# ARA_Cartridge_V4.net
KiCad netlist of a schematic drawn in EAGLE
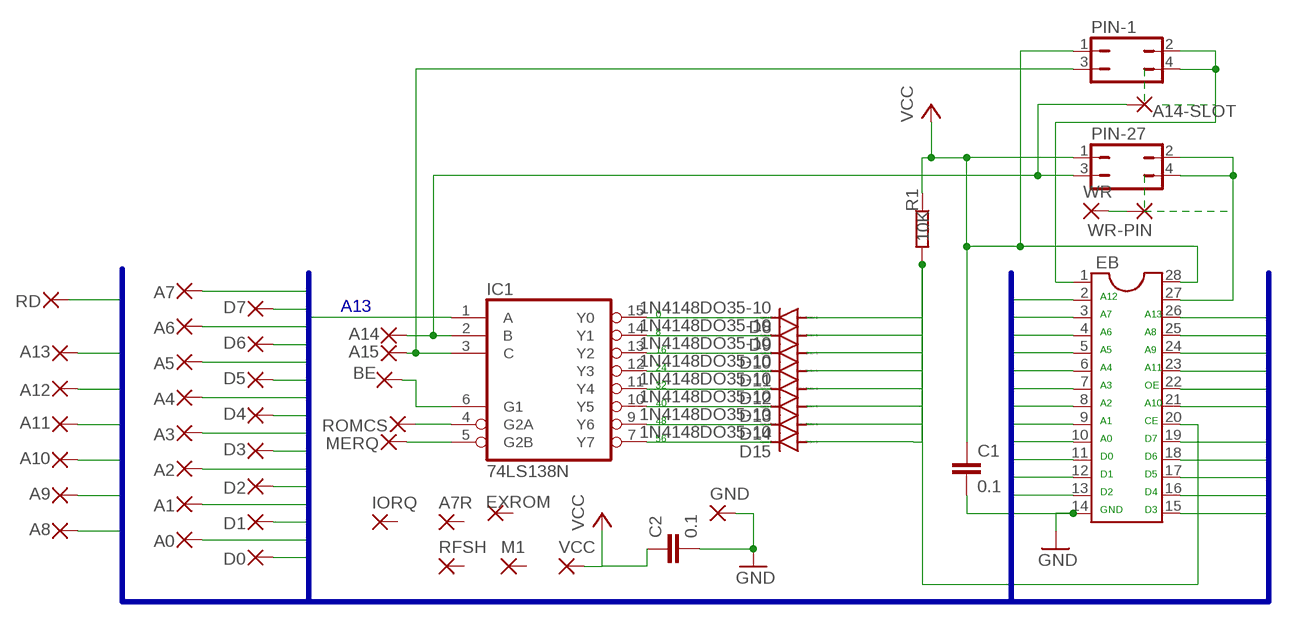
[diagram p0: schematic, sheet 1]

(export (version "E")
  (design (tool "Eeschema 10.0.6"))
  (components
    (comp (ref "A0")
      (value "SMD2")
      (footprint "eagle-import:SMD2")
      (libsource (lib "eagle-import") (part "SMD2"))
    )
    (comp (ref "A1")
      (value "SMD2")
      (footprint "eagle-import:SMD2")
      (libsource (lib "eagle-import") (part "SMD2"))
    )
    (comp (ref "A2")
      (value "SMD2")
      (footprint "eagle-import:SMD2")
      (libsource (lib "eagle-import") (part "SMD2"))
    )
    (comp (ref "A3")
      (value "SMD2")
      (footprint "eagle-import:SMD2")
      (libsource (lib "eagle-import") (part "SMD2"))
    )
    (comp (ref "A4")
      (value "SMD2")
      (footprint "eagle-import:SMD2")
      (libsource (lib "eagle-import") (part "SMD2"))
    )
    (comp (ref "A5")
      (value "SMD2")
      (footprint "eagle-import:SMD2")
      (libsource (lib "eagle-import") (part "SMD2"))
    )
    (comp (ref "A6")
      (value "SMD2")
      (footprint "eagle-import:SMD2")
      (libsource (lib "eagle-import") (part "SMD2"))
    )
    (comp (ref "A7")
      (value "SMD2")
      (footprint "eagle-import:SMD2")
      (libsource (lib "eagle-import") (part "SMD2"))
    )
    (comp (ref "A7R")
      (value "SMD2")
      (footprint "eagle-import:SMD2")
      (libsource (lib "eagle-import") (part "SMD2"))
    )
    (comp (ref "A8")
      (value "SMD2")
      (footprint "eagle-import:SMD2")
      (libsource (lib "eagle-import") (part "SMD2"))
    )
    (comp (ref "A9")
      (value "SMD2")
      (footprint "eagle-import:SMD2")
      (libsource (lib "eagle-import") (part "SMD2"))
    )
    (comp (ref "A10")
      (value "SMD2")
      (footprint "eagle-import:SMD2")
      (libsource (lib "eagle-import") (part "SMD2"))
    )
    (comp (ref "A11")
      (value "SMD2")
      (footprint "eagle-import:SMD2")
      (libsource (lib "eagle-import") (part "SMD2"))
    )
    (comp (ref "A12")
      (value "SMD2")
      (footprint "eagle-import:SMD2")
      (libsource (lib "eagle-import") (part "SMD2"))
    )
    (comp (ref "A13")
      (value "SMD2")
      (footprint "eagle-import:SMD2")
      (libsource (lib "eagle-import") (part "SMD2"))
    )
    (comp (ref "A14")
      (value "SMD2")
      (footprint "eagle-import:SMD2")
      (libsource (lib "eagle-import") (part "SMD2"))
    )
    (comp (ref "A14-SLOT")
      (value "1,6/0,8")
      (footprint "eagle-import:1,6_0,8")
      (libsource (lib "eagle-import") (part "1,6/0,8"))
    )
    (comp (ref "A15")
      (value "SMD2")
      (footprint "eagle-import:SMD2")
      (libsource (lib "eagle-import") (part "SMD2"))
    )
    (comp (ref "BE")
      (value "SMD2")
      (footprint "eagle-import:SMD2")
      (libsource (lib "eagle-import") (part "SMD2"))
    )
    (comp (ref "C1")
      (value "0.1")
      (footprint "eagle-import:C2.5-3")
      (libsource (lib "eagle-import") (part "C2,5-3"))
    )
    (comp (ref "C2")
      (value "0.1")
      (footprint "eagle-import:C2.5-3")
      (libsource (lib "eagle-import") (part "C2,5-3"))
    )
    (comp (ref "D0")
      (value "SMD2")
      (footprint "eagle-import:SMD2")
      (libsource (lib "eagle-import") (part "SMD2"))
    )
    (comp (ref "D1")
      (value "SMD2")
      (footprint "eagle-import:SMD2")
      (libsource (lib "eagle-import") (part "SMD2"))
    )
    (comp (ref "D2")
      (value "SMD2")
      (footprint "eagle-import:SMD2")
      (libsource (lib "eagle-import") (part "SMD2"))
    )
    (comp (ref "D3")
      (value "SMD2")
      (footprint "eagle-import:SMD2")
      (libsource (lib "eagle-import") (part "SMD2"))
    )
    (comp (ref "D4")
      (value "SMD2")
      (footprint "eagle-import:SMD2")
      (libsource (lib "eagle-import") (part "SMD2"))
    )
    (comp (ref "D5")
      (value "SMD2")
      (footprint "eagle-import:SMD2")
      (libsource (lib "eagle-import") (part "SMD2"))
    )
    (comp (ref "D6")
      (value "SMD2")
      (footprint "eagle-import:SMD2")
      (libsource (lib "eagle-import") (part "SMD2"))
    )
    (comp (ref "D7")
      (value "SMD2")
      (footprint "eagle-import:SMD2")
      (libsource (lib "eagle-import") (part "SMD2"))
    )
    (comp (ref "D8")
      (value "1N4148DO35-10")
      (footprint "eagle-import:DO35-10")
      (libsource (lib "eagle-import") (part "1N4148DO35-10"))
    )
    (comp (ref "D9")
      (value "1N4148DO35-10")
      (footprint "eagle-import:DO35-10")
      (libsource (lib "eagle-import") (part "1N4148DO35-10"))
    )
    (comp (ref "D10")
      (value "1N4148DO35-10")
      (footprint "eagle-import:DO35-10")
      (libsource (lib "eagle-import") (part "1N4148DO35-10"))
    )
    (comp (ref "D11")
      (value "1N4148DO35-10")
      (footprint "eagle-import:DO35-10")
      (libsource (lib "eagle-import") (part "1N4148DO35-10"))
    )
    (comp (ref "D12")
      (value "1N4148DO35-10")
      (footprint "eagle-import:DO35-10")
      (libsource (lib "eagle-import") (part "1N4148DO35-10"))
    )
    (comp (ref "D13")
      (value "1N4148DO35-10")
      (footprint "eagle-import:DO35-10")
      (libsource (lib "eagle-import") (part "1N4148DO35-10"))
    )
    (comp (ref "D14")
      (value "1N4148DO35-10")
      (footprint "eagle-import:DO35-10")
      (libsource (lib "eagle-import") (part "1N4148DO35-10"))
    )
    (comp (ref "D15")
      (value "1N4148DO35-10")
      (footprint "eagle-import:DO35-10")
      (libsource (lib "eagle-import") (part "1N4148DO35-10"))
    )
    (comp (ref "EB")
      (value "DIL28")
      (footprint "eagle-import:DIL28-6")
      (libsource (lib "eagle-import") (part "DIL28"))
    )
    (comp (ref "EXROM")
      (value "SMD2")
      (footprint "eagle-import:SMD2")
      (libsource (lib "eagle-import") (part "SMD2"))
    )
    (comp (ref "GND")
      (value "SMD2")
      (footprint "eagle-import:SMD2")
      (libsource (lib "eagle-import") (part "SMD2"))
    )
    (comp (ref "IC1")
      (value "74LS138N")
      (footprint "eagle-import:DIL16")
      (libsource (lib "eagle-import") (part "74138NLS"))
    )
    (comp (ref "IORQ")
      (value "SMD2")
      (footprint "eagle-import:SMD2")
      (libsource (lib "eagle-import") (part "SMD2"))
    )
    (comp (ref "M1")
      (value "SMD2")
      (footprint "eagle-import:SMD2")
      (libsource (lib "eagle-import") (part "SMD2"))
    )
    (comp (ref "MERQ")
      (value "SMD2")
      (footprint "eagle-import:SMD2")
      (libsource (lib "eagle-import") (part "SMD2"))
    )
    (comp (ref "PIN-1")
      (value "JP2Q")
      (footprint "eagle-import:JP2Q")
      (libsource (lib "eagle-import") (part "JP2Q"))
    )
    (comp (ref "PIN-27")
      (value "JP2Q")
      (footprint "eagle-import:JP2Q")
      (libsource (lib "eagle-import") (part "JP2Q"))
    )
    (comp (ref "R1")
      (value "10K")
      (footprint "eagle-import:0207_10")
      (libsource (lib "eagle-import") (part "R-EU_0207/10"))
    )
    (comp (ref "RD")
      (value "SMD2")
      (footprint "eagle-import:SMD2")
      (libsource (lib "eagle-import") (part "SMD2"))
    )
    (comp (ref "RFSH")
      (value "SMD2")
      (footprint "eagle-import:SMD2")
      (libsource (lib "eagle-import") (part "SMD2"))
    )
    (comp (ref "ROMCS")
      (value "SMD2")
      (footprint "eagle-import:SMD2")
      (libsource (lib "eagle-import") (part "SMD2"))
    )
    (comp (ref "VCC")
      (value "SMD2")
      (footprint "eagle-import:SMD2")
      (libsource (lib "eagle-import") (part "SMD2"))
    )
    (comp (ref "WR")
      (value "SMD2")
      (footprint "eagle-import:SMD2")
      (libsource (lib "eagle-import") (part "SMD2"))
    )
    (comp (ref "WR-PIN")
      (value "1,6/0,8")
      (footprint "eagle-import:1,6_0,8")
      (libsource (lib "eagle-import") (part "1,6/0,8"))
    )
  )
  (nets
    (net (code "1") (name "/A0") (class "Default")
      (node (ref "A0") (pin "1") (pinfunction "P_1") (pintype "passive"))
      (node (ref "EB") (pin "10") (pinfunction "10_10") (pintype "passive"))
    )
    (net (code "2") (name "/A1") (class "Default")
      (node (ref "A1") (pin "1") (pinfunction "P_1") (pintype "passive"))
      (node (ref "EB") (pin "9") (pinfunction "9_9") (pintype "passive"))
    )
    (net (code "3") (name "/A2") (class "Default")
      (node (ref "A2") (pin "1") (pinfunction "P_1") (pintype "passive"))
      (node (ref "EB") (pin "8") (pinfunction "8_8") (pintype "passive"))
    )
    (net (code "4") (name "/A3") (class "Default")
      (node (ref "A3") (pin "1") (pinfunction "P_1") (pintype "passive"))
      (node (ref "EB") (pin "7") (pinfunction "7_7") (pintype "passive"))
    )
    (net (code "5") (name "/A4") (class "Default")
      (node (ref "A4") (pin "1") (pinfunction "P_1") (pintype "passive"))
      (node (ref "EB") (pin "6") (pinfunction "6_6") (pintype "passive"))
    )
    (net (code "6") (name "/A5") (class "Default")
      (node (ref "A5") (pin "1") (pinfunction "P_1") (pintype "passive"))
      (node (ref "EB") (pin "5") (pinfunction "5_5") (pintype "passive"))
    )
    (net (code "7") (name "/A6") (class "Default")
      (node (ref "A6") (pin "1") (pinfunction "P_1") (pintype "passive"))
      (node (ref "EB") (pin "4") (pinfunction "4_4") (pintype "passive"))
    )
    (net (code "8") (name "/A7") (class "Default")
      (node (ref "A7") (pin "1") (pinfunction "P_1") (pintype "passive"))
      (node (ref "EB") (pin "3") (pinfunction "3_3") (pintype "passive"))
    )
    (net (code "9") (name "/A8") (class "Default")
      (node (ref "A8") (pin "1") (pinfunction "P_1") (pintype "passive"))
      (node (ref "EB") (pin "25") (pinfunction "25_25") (pintype "passive"))
    )
    (net (code "10") (name "/A9") (class "Default")
      (node (ref "A9") (pin "1") (pinfunction "P_1") (pintype "passive"))
      (node (ref "EB") (pin "24") (pinfunction "24_24") (pintype "passive"))
    )
    (net (code "11") (name "/A10") (class "Default")
      (node (ref "A10") (pin "1") (pinfunction "P_1") (pintype "passive"))
      (node (ref "EB") (pin "21") (pinfunction "21_21") (pintype "passive"))
    )
    (net (code "12") (name "/A11") (class "Default")
      (node (ref "A11") (pin "1") (pinfunction "P_1") (pintype "passive"))
      (node (ref "EB") (pin "23") (pinfunction "23_23") (pintype "passive"))
    )
    (net (code "13") (name "/A12") (class "Default")
      (node (ref "A12") (pin "1") (pinfunction "P_1") (pintype "passive"))
      (node (ref "EB") (pin "2") (pinfunction "2_2") (pintype "passive"))
    )
    (net (code "14") (name "/A13") (class "Default")
      (node (ref "A13") (pin "1") (pinfunction "P_1") (pintype "passive"))
      (node (ref "EB") (pin "26") (pinfunction "26_26") (pintype "passive"))
      (node (ref "IC1") (pin "1") (pinfunction "A_1") (pintype "input"))
    )
    (net (code "15") (name "/D0") (class "Default")
      (node (ref "D0") (pin "1") (pinfunction "P_1") (pintype "passive"))
      (node (ref "EB") (pin "11") (pinfunction "11_11") (pintype "passive"))
    )
    (net (code "16") (name "/D1") (class "Default")
      (node (ref "D1") (pin "1") (pinfunction "P_1") (pintype "passive"))
      (node (ref "EB") (pin "12") (pinfunction "12_12") (pintype "passive"))
    )
    (net (code "17") (name "/D2") (class "Default")
      (node (ref "D2") (pin "1") (pinfunction "P_1") (pintype "passive"))
      (node (ref "EB") (pin "13") (pinfunction "13_13") (pintype "passive"))
    )
    (net (code "18") (name "/D3") (class "Default")
      (node (ref "D3") (pin "1") (pinfunction "P_1") (pintype "passive"))
      (node (ref "EB") (pin "15") (pinfunction "15_15") (pintype "passive"))
    )
    (net (code "19") (name "/D4") (class "Default")
      (node (ref "D4") (pin "1") (pinfunction "P_1") (pintype "passive"))
      (node (ref "EB") (pin "16") (pinfunction "16_16") (pintype "passive"))
    )
    (net (code "20") (name "/D5") (class "Default")
      (node (ref "D5") (pin "1") (pinfunction "P_1") (pintype "passive"))
      (node (ref "EB") (pin "17") (pinfunction "17_17") (pintype "passive"))
    )
    (net (code "21") (name "/D6") (class "Default")
      (node (ref "D6") (pin "1") (pinfunction "P_1") (pintype "passive"))
      (node (ref "EB") (pin "18") (pinfunction "18_18") (pintype "passive"))
    )
    (net (code "22") (name "/D7") (class "Default")
      (node (ref "D7") (pin "1") (pinfunction "P_1") (pintype "passive"))
      (node (ref "EB") (pin "19") (pinfunction "19_19") (pintype "passive"))
    )
    (net (code "23") (name "/RD") (class "Default")
      (node (ref "EB") (pin "22") (pinfunction "22_22") (pintype "passive"))
      (node (ref "RD") (pin "1") (pinfunction "P_1") (pintype "passive"))
    )
    (net (code "24") (name "GND") (class "Default")
      (node (ref "C1") (pin "2") (pinfunction "2_2") (pintype "passive"))
      (node (ref "C2") (pin "2") (pinfunction "2_2") (pintype "passive"))
      (node (ref "EB") (pin "14") (pinfunction "14_14") (pintype "passive"))
      (node (ref "GND") (pin "1") (pinfunction "P_1") (pintype "passive"))
    )
    (net (code "25") (name "Net-(A14-P)") (class "Default")
      (node (ref "A14") (pin "1") (pinfunction "P_1") (pintype "passive"))
      (node (ref "A14-SLOT") (pin "1") (pinfunction "P_1") (pintype "passive"))
      (node (ref "IC1") (pin "2") (pinfunction "B_2") (pintype "input"))
      (node (ref "PIN-27") (pin "3") (pinfunction "3_3") (pintype "passive"))
    )
    (net (code "26") (name "Net-(A15-P)") (class "Default")
      (node (ref "A15") (pin "1") (pinfunction "P_1") (pintype "passive"))
      (node (ref "IC1") (pin "3") (pinfunction "C_3") (pintype "input"))
      (node (ref "PIN-1") (pin "3") (pinfunction "3_3") (pintype "passive"))
    )
    (net (code "27") (name "Net-(BE-P)") (class "Default")
      (node (ref "BE") (pin "1") (pinfunction "P_1") (pintype "passive"))
      (node (ref "IC1") (pin "6") (pinfunction "G1_6") (pintype "input"))
    )
    (net (code "28") (name "Net-(D10-PadA)") (class "Default")
      (node (ref "D10") (pin "A") (pinfunction "A_A") (pintype "passive"))
      (node (ref "D11") (pin "A") (pinfunction "A_A") (pintype "passive"))
      (node (ref "D12") (pin "A") (pinfunction "A_A") (pintype "passive"))
      (node (ref "D13") (pin "A") (pinfunction "A_A") (pintype "passive"))
      (node (ref "D14") (pin "A") (pinfunction "A_A") (pintype "passive"))
      (node (ref "D15") (pin "A") (pinfunction "A_A") (pintype "passive"))
      (node (ref "D8") (pin "A") (pinfunction "A_A") (pintype "passive"))
      (node (ref "D9") (pin "A") (pinfunction "A_A") (pintype "passive"))
      (node (ref "EB") (pin "20") (pinfunction "20_20") (pintype "passive"))
      (node (ref "R1") (pin "2") (pinfunction "2_2") (pintype "passive"))
    )
    (net (code "29") (name "Net-(EB-Pad1)") (class "Default")
      (node (ref "EB") (pin "1") (pinfunction "1_1") (pintype "passive"))
      (node (ref "PIN-1") (pin "2") (pinfunction "2_2") (pintype "passive"))
      (node (ref "PIN-1") (pin "4") (pinfunction "4_4") (pintype "passive"))
    )
    (net (code "30") (name "Net-(EB-Pad27)") (class "Default")
      (node (ref "EB") (pin "27") (pinfunction "27_27") (pintype "passive"))
      (node (ref "PIN-27") (pin "2") (pinfunction "2_2") (pintype "passive"))
      (node (ref "PIN-27") (pin "4") (pinfunction "4_4") (pintype "passive"))
    )
    (net (code "31") (name "Net-(IC1A-G2A)") (class "Default")
      (node (ref "IC1") (pin "4") (pinfunction "G2A_4") (pintype "input"))
      (node (ref "ROMCS") (pin "1") (pinfunction "P_1") (pintype "passive"))
    )
    (net (code "32") (name "Net-(IC1A-G2B)") (class "Default")
      (node (ref "IC1") (pin "5") (pinfunction "G2B_5") (pintype "input"))
      (node (ref "MERQ") (pin "1") (pinfunction "P_1") (pintype "passive"))
    )
    (net (code "33") (name "Net-(IC1A-Y0)") (class "Default")
      (node (ref "D8") (pin "C") (pinfunction "C_C") (pintype "passive"))
      (node (ref "IC1") (pin "15") (pinfunction "Y0_15") (pintype "output"))
    )
    (net (code "34") (name "Net-(IC1A-Y1)") (class "Default")
      (node (ref "D9") (pin "C") (pinfunction "C_C") (pintype "passive"))
      (node (ref "IC1") (pin "14") (pinfunction "Y1_14") (pintype "output"))
    )
    (net (code "35") (name "Net-(IC1A-Y2)") (class "Default")
      (node (ref "D10") (pin "C") (pinfunction "C_C") (pintype "passive"))
      (node (ref "IC1") (pin "13") (pinfunction "Y2_13") (pintype "output"))
    )
    (net (code "36") (name "Net-(IC1A-Y3)") (class "Default")
      (node (ref "D11") (pin "C") (pinfunction "C_C") (pintype "passive"))
      (node (ref "IC1") (pin "12") (pinfunction "Y3_12") (pintype "output"))
    )
    (net (code "37") (name "Net-(IC1A-Y4)") (class "Default")
      (node (ref "D12") (pin "C") (pinfunction "C_C") (pintype "passive"))
      (node (ref "IC1") (pin "11") (pinfunction "Y4_11") (pintype "output"))
    )
    (net (code "38") (name "Net-(IC1A-Y5)") (class "Default")
      (node (ref "D13") (pin "C") (pinfunction "C_C") (pintype "passive"))
      (node (ref "IC1") (pin "10") (pinfunction "Y5_10") (pintype "output"))
    )
    (net (code "39") (name "Net-(IC1A-Y6)") (class "Default")
      (node (ref "D14") (pin "C") (pinfunction "C_C") (pintype "passive"))
      (node (ref "IC1") (pin "9") (pinfunction "Y6_9") (pintype "output"))
    )
    (net (code "40") (name "Net-(IC1A-Y7)") (class "Default")
      (node (ref "D15") (pin "C") (pinfunction "C_C") (pintype "passive"))
      (node (ref "IC1") (pin "7") (pinfunction "Y7_7") (pintype "output"))
    )
    (net (code "41") (name "Net-(WR-P)") (class "Default")
      (node (ref "WR") (pin "1") (pinfunction "P_1") (pintype "passive"))
      (node (ref "WR-PIN") (pin "1") (pinfunction "P_1") (pintype "passive"))
    )
    (net (code "42") (name "VCC") (class "Default")
      (node (ref "C1") (pin "1") (pinfunction "1_1") (pintype "passive"))
      (node (ref "C2") (pin "1") (pinfunction "1_1") (pintype "passive"))
      (node (ref "EB") (pin "28") (pinfunction "28_28") (pintype "passive"))
      (node (ref "PIN-1") (pin "1") (pinfunction "1_1") (pintype "passive"))
      (node (ref "PIN-27") (pin "1") (pinfunction "1_1") (pintype "passive"))
      (node (ref "R1") (pin "1") (pinfunction "1_1") (pintype "passive"))
      (node (ref "VCC") (pin "1") (pinfunction "P_1") (pintype "passive"))
    )
    (net (code "43") (name "unconnected-(A7R-P-Pad1)") (class "Default")
      (node (ref "A7R") (pin "1") (pinfunction "P_1") (pintype "passive"))
    )
    (net (code "44") (name "unconnected-(EXROM-P-Pad1)") (class "Default")
      (node (ref "EXROM") (pin "1") (pinfunction "P_1") (pintype "passive"))
    )
    (net (code "45") (name "unconnected-(IORQ-P-Pad1)") (class "Default")
      (node (ref "IORQ") (pin "1") (pinfunction "P_1") (pintype "passive"))
    )
    (net (code "46") (name "unconnected-(M1-P-Pad1)") (class "Default")
      (node (ref "M1") (pin "1") (pinfunction "P_1") (pintype "passive"))
    )
    (net (code "47") (name "unconnected-(RFSH-P-Pad1)") (class "Default")
      (node (ref "RFSH") (pin "1") (pinfunction "P_1") (pintype "passive"))
    )
  )
)
